# main_board.net
KiCad netlist of a schematic drawn in EAGLE
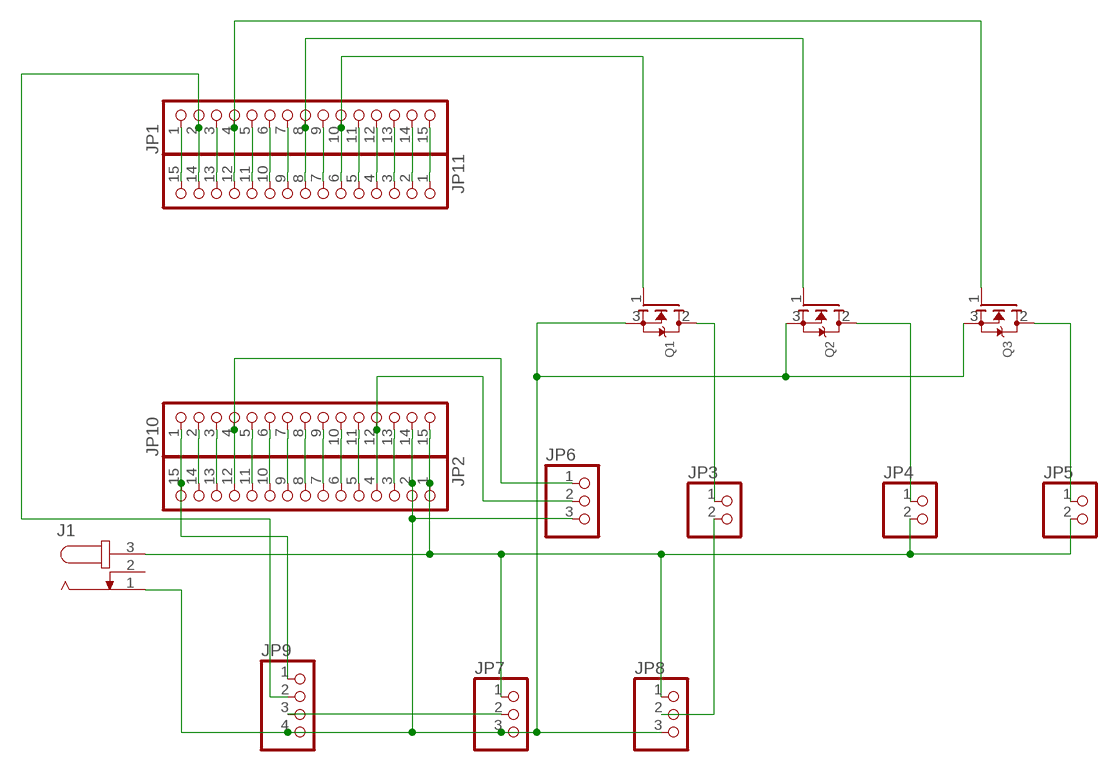
[diagram p0: schematic, sheet 1]

(export (version "E")
  (design (tool "Eeschema 10.0.6"))
  (components
    (comp (ref "J1")
      (value "JACK-PLUG1")
      (footprint "eagle-import:SPC4078")
      (libsource (lib "eagle-import") (part "JACK-PLUG1"))
    )
    (comp (ref "JP1")
      (value "PINHD-1X15")
      (footprint "eagle-import:1X15")
      (libsource (lib "eagle-import") (part "PINHD-1X15"))
    )
    (comp (ref "JP2")
      (value "PINHD-1X15")
      (footprint "eagle-import:1X15")
      (libsource (lib "eagle-import") (part "PINHD-1X15"))
    )
    (comp (ref "JP3")
      (value "PINHD-1X2")
      (footprint "eagle-import:1X02")
      (libsource (lib "eagle-import") (part "PINHD-1X2"))
    )
    (comp (ref "JP4")
      (value "PINHD-1X2")
      (footprint "eagle-import:1X02")
      (libsource (lib "eagle-import") (part "PINHD-1X2"))
    )
    (comp (ref "JP5")
      (value "PINHD-1X2")
      (footprint "eagle-import:1X02")
      (libsource (lib "eagle-import") (part "PINHD-1X2"))
    )
    (comp (ref "JP6")
      (value "PINHD-1X3")
      (footprint "eagle-import:1X03")
      (libsource (lib "eagle-import") (part "PINHD-1X3"))
    )
    (comp (ref "JP7")
      (value "PINHD-1X3")
      (footprint "eagle-import:1X03")
      (libsource (lib "eagle-import") (part "PINHD-1X3"))
    )
    (comp (ref "JP8")
      (value "PINHD-1X3")
      (footprint "eagle-import:1X03")
      (libsource (lib "eagle-import") (part "PINHD-1X3"))
    )
    (comp (ref "JP9")
      (value "PINHD-1X4")
      (footprint "eagle-import:1X04")
      (libsource (lib "eagle-import") (part "PINHD-1X4"))
    )
    (comp (ref "JP10")
      (value "PINHD-1X15")
      (footprint "eagle-import:1X15")
      (libsource (lib "eagle-import") (part "PINHD-1X15"))
    )
    (comp (ref "JP11")
      (value "PINHD-1X15")
      (footprint "eagle-import:1X15")
      (libsource (lib "eagle-import") (part "PINHD-1X15"))
    )
    (comp (ref "Q1")
      (value "MOSFET-NGDS_TO220V")
      (footprint "eagle-import:TO220V")
      (libsource (lib "eagle-import") (part "MOSFET-NGDS_TO220V"))
    )
    (comp (ref "Q2")
      (value "MOSFET-NGDS_TO220V")
      (footprint "eagle-import:TO220V")
      (libsource (lib "eagle-import") (part "MOSFET-NGDS_TO220V"))
    )
    (comp (ref "Q3")
      (value "MOSFET-NGDS_TO220V")
      (footprint "eagle-import:TO220V")
      (libsource (lib "eagle-import") (part "MOSFET-NGDS_TO220V"))
    )
  )
  (nets
    (net (code "1") (name "Net-(J1-Pad3)") (class "Default")
      (node (ref "J1") (pin "3") (pinfunction "3_3") (pintype "passive"))
      (node (ref "JP10") (pin "15") (pinfunction "15_15") (pintype "passive"))
      (node (ref "JP2") (pin "1") (pinfunction "1_1") (pintype "passive"))
      (node (ref "JP4") (pin "2") (pinfunction "2_2") (pintype "passive"))
      (node (ref "JP5") (pin "2") (pinfunction "2_2") (pintype "passive"))
      (node (ref "JP7") (pin "1") (pinfunction "1_1") (pintype "passive"))
      (node (ref "JP8") (pin "1") (pinfunction "1_1") (pintype "passive"))
    )
    (net (code "2") (name "Net-(JP1-Pad1)") (class "Default")
      (node (ref "JP1") (pin "1") (pinfunction "1_1") (pintype "passive"))
      (node (ref "JP11") (pin "15") (pinfunction "15_15") (pintype "passive"))
    )
    (net (code "3") (name "Net-(JP1-Pad2)") (class "Default")
      (node (ref "JP1") (pin "2") (pinfunction "2_2") (pintype "passive"))
      (node (ref "JP11") (pin "14") (pinfunction "14_14") (pintype "passive"))
      (node (ref "JP9") (pin "2") (pinfunction "2_2") (pintype "passive"))
    )
    (net (code "4") (name "Net-(JP1-Pad3)") (class "Default")
      (node (ref "JP1") (pin "3") (pinfunction "3_3") (pintype "passive"))
      (node (ref "JP11") (pin "13") (pinfunction "13_13") (pintype "passive"))
    )
    (net (code "5") (name "Net-(JP1-Pad5)") (class "Default")
      (node (ref "JP1") (pin "5") (pinfunction "5_5") (pintype "passive"))
      (node (ref "JP11") (pin "11") (pinfunction "11_11") (pintype "passive"))
    )
    (net (code "6") (name "Net-(JP1-Pad6)") (class "Default")
      (node (ref "JP1") (pin "6") (pinfunction "6_6") (pintype "passive"))
      (node (ref "JP11") (pin "10") (pinfunction "10_10") (pintype "passive"))
    )
    (net (code "7") (name "Net-(JP1-Pad7)") (class "Default")
      (node (ref "JP1") (pin "7") (pinfunction "7_7") (pintype "passive"))
      (node (ref "JP11") (pin "9") (pinfunction "9_9") (pintype "passive"))
    )
    (net (code "8") (name "Net-(JP1-Pad9)") (class "Default")
      (node (ref "JP1") (pin "9") (pinfunction "9_9") (pintype "passive"))
      (node (ref "JP11") (pin "7") (pinfunction "7_7") (pintype "passive"))
    )
    (net (code "9") (name "Net-(JP1-Pad11)") (class "Default")
      (node (ref "JP1") (pin "11") (pinfunction "11_11") (pintype "passive"))
      (node (ref "JP11") (pin "5") (pinfunction "5_5") (pintype "passive"))
    )
    (net (code "10") (name "Net-(JP1-Pad12)") (class "Default")
      (node (ref "JP1") (pin "12") (pinfunction "12_12") (pintype "passive"))
      (node (ref "JP11") (pin "4") (pinfunction "4_4") (pintype "passive"))
    )
    (net (code "11") (name "Net-(JP1-Pad13)") (class "Default")
      (node (ref "JP1") (pin "13") (pinfunction "13_13") (pintype "passive"))
      (node (ref "JP11") (pin "3") (pinfunction "3_3") (pintype "passive"))
    )
    (net (code "12") (name "Net-(JP1-Pad14)") (class "Default")
      (node (ref "JP1") (pin "14") (pinfunction "14_14") (pintype "passive"))
      (node (ref "JP11") (pin "2") (pinfunction "2_2") (pintype "passive"))
    )
    (net (code "13") (name "Net-(JP1-Pad15)") (class "Default")
      (node (ref "JP1") (pin "15") (pinfunction "15_15") (pintype "passive"))
      (node (ref "JP11") (pin "1") (pinfunction "1_1") (pintype "passive"))
    )
    (net (code "14") (name "Net-(JP3-Pad2)") (class "Default")
      (node (ref "JP3") (pin "2") (pinfunction "2_2") (pintype "passive"))
      (node (ref "JP8") (pin "2") (pinfunction "2_2") (pintype "passive"))
    )
    (net (code "15") (name "Net-(JP7-Pad2)") (class "Default")
      (node (ref "JP7") (pin "2") (pinfunction "2_2") (pintype "passive"))
      (node (ref "JP9") (pin "3") (pinfunction "3_3") (pintype "passive"))
    )
    (net (code "16") (name "Net-(JP10-Pad1)") (class "Default")
      (node (ref "JP10") (pin "1") (pinfunction "1_1") (pintype "passive"))
      (node (ref "JP2") (pin "15") (pinfunction "15_15") (pintype "passive"))
      (node (ref "JP9") (pin "1") (pinfunction "1_1") (pintype "passive"))
    )
    (net (code "17") (name "Net-(JP10-Pad2)") (class "Default")
      (node (ref "JP10") (pin "2") (pinfunction "2_2") (pintype "passive"))
      (node (ref "JP2") (pin "14") (pinfunction "14_14") (pintype "passive"))
    )
    (net (code "18") (name "Net-(JP10-Pad3)") (class "Default")
      (node (ref "JP10") (pin "3") (pinfunction "3_3") (pintype "passive"))
      (node (ref "JP2") (pin "13") (pinfunction "13_13") (pintype "passive"))
    )
    (net (code "19") (name "Net-(JP10-Pad4)") (class "Default")
      (node (ref "JP10") (pin "4") (pinfunction "4_4") (pintype "passive"))
      (node (ref "JP2") (pin "12") (pinfunction "12_12") (pintype "passive"))
      (node (ref "JP6") (pin "1") (pinfunction "1_1") (pintype "passive"))
    )
    (net (code "20") (name "Net-(JP10-Pad5)") (class "Default")
      (node (ref "JP10") (pin "5") (pinfunction "5_5") (pintype "passive"))
      (node (ref "JP2") (pin "11") (pinfunction "11_11") (pintype "passive"))
    )
    (net (code "21") (name "Net-(JP10-Pad6)") (class "Default")
      (node (ref "JP10") (pin "6") (pinfunction "6_6") (pintype "passive"))
      (node (ref "JP2") (pin "10") (pinfunction "10_10") (pintype "passive"))
    )
    (net (code "22") (name "Net-(JP10-Pad7)") (class "Default")
      (node (ref "JP10") (pin "7") (pinfunction "7_7") (pintype "passive"))
      (node (ref "JP2") (pin "9") (pinfunction "9_9") (pintype "passive"))
    )
    (net (code "23") (name "Net-(JP10-Pad8)") (class "Default")
      (node (ref "JP10") (pin "8") (pinfunction "8_8") (pintype "passive"))
      (node (ref "JP2") (pin "8") (pinfunction "8_8") (pintype "passive"))
    )
    (net (code "24") (name "Net-(JP10-Pad9)") (class "Default")
      (node (ref "JP10") (pin "9") (pinfunction "9_9") (pintype "passive"))
      (node (ref "JP2") (pin "7") (pinfunction "7_7") (pintype "passive"))
    )
    (net (code "25") (name "Net-(JP10-Pad10)") (class "Default")
      (node (ref "JP10") (pin "10") (pinfunction "10_10") (pintype "passive"))
      (node (ref "JP2") (pin "6") (pinfunction "6_6") (pintype "passive"))
    )
    (net (code "26") (name "Net-(JP10-Pad11)") (class "Default")
      (node (ref "JP10") (pin "11") (pinfunction "11_11") (pintype "passive"))
      (node (ref "JP2") (pin "5") (pinfunction "5_5") (pintype "passive"))
    )
    (net (code "27") (name "Net-(JP10-Pad12)") (class "Default")
      (node (ref "JP10") (pin "12") (pinfunction "12_12") (pintype "passive"))
      (node (ref "JP2") (pin "4") (pinfunction "4_4") (pintype "passive"))
      (node (ref "JP6") (pin "2") (pinfunction "2_2") (pintype "passive"))
    )
    (net (code "28") (name "Net-(JP10-Pad13)") (class "Default")
      (node (ref "JP10") (pin "13") (pinfunction "13_13") (pintype "passive"))
      (node (ref "JP2") (pin "3") (pinfunction "3_3") (pintype "passive"))
    )
    (net (code "29") (name "Net-(Q1-D)") (class "Default")
      (node (ref "JP3") (pin "1") (pinfunction "1_1") (pintype "passive"))
      (node (ref "Q1") (pin "2") (pinfunction "D_2") (pintype "bidirectional"))
    )
    (net (code "30") (name "Net-(Q1-G)") (class "Default")
      (node (ref "JP1") (pin "10") (pinfunction "10_10") (pintype "passive"))
      (node (ref "JP11") (pin "6") (pinfunction "6_6") (pintype "passive"))
      (node (ref "Q1") (pin "1") (pinfunction "G_1") (pintype "bidirectional"))
    )
    (net (code "31") (name "Net-(Q1-S)") (class "Default")
      (node (ref "J1") (pin "1") (pinfunction "1_1") (pintype "passive"))
      (node (ref "JP10") (pin "14") (pinfunction "14_14") (pintype "passive"))
      (node (ref "JP2") (pin "2") (pinfunction "2_2") (pintype "passive"))
      (node (ref "JP6") (pin "3") (pinfunction "3_3") (pintype "passive"))
      (node (ref "JP7") (pin "3") (pinfunction "3_3") (pintype "passive"))
      (node (ref "JP8") (pin "3") (pinfunction "3_3") (pintype "passive"))
      (node (ref "JP9") (pin "4") (pinfunction "4_4") (pintype "passive"))
      (node (ref "Q1") (pin "3") (pinfunction "S_3") (pintype "bidirectional"))
      (node (ref "Q2") (pin "3") (pinfunction "S_3") (pintype "bidirectional"))
      (node (ref "Q3") (pin "3") (pinfunction "S_3") (pintype "bidirectional"))
    )
    (net (code "32") (name "Net-(Q2-D)") (class "Default")
      (node (ref "JP4") (pin "1") (pinfunction "1_1") (pintype "passive"))
      (node (ref "Q2") (pin "2") (pinfunction "D_2") (pintype "bidirectional"))
    )
    (net (code "33") (name "Net-(Q2-G)") (class "Default")
      (node (ref "JP1") (pin "8") (pinfunction "8_8") (pintype "passive"))
      (node (ref "JP11") (pin "8") (pinfunction "8_8") (pintype "passive"))
      (node (ref "Q2") (pin "1") (pinfunction "G_1") (pintype "bidirectional"))
    )
    (net (code "34") (name "Net-(Q3-D)") (class "Default")
      (node (ref "JP5") (pin "1") (pinfunction "1_1") (pintype "passive"))
      (node (ref "Q3") (pin "2") (pinfunction "D_2") (pintype "bidirectional"))
    )
    (net (code "35") (name "Net-(Q3-G)") (class "Default")
      (node (ref "JP1") (pin "4") (pinfunction "4_4") (pintype "passive"))
      (node (ref "JP11") (pin "12") (pinfunction "12_12") (pintype "passive"))
      (node (ref "Q3") (pin "1") (pinfunction "G_1") (pintype "bidirectional"))
    )
    (net (code "36") (name "unconnected-(J1-Pad2)") (class "Default")
      (node (ref "J1") (pin "2") (pinfunction "2_2") (pintype "passive"))
    )
  )
)
